# PhotoSensor.net
KiCad netlist of a schematic drawn in Altium Designer
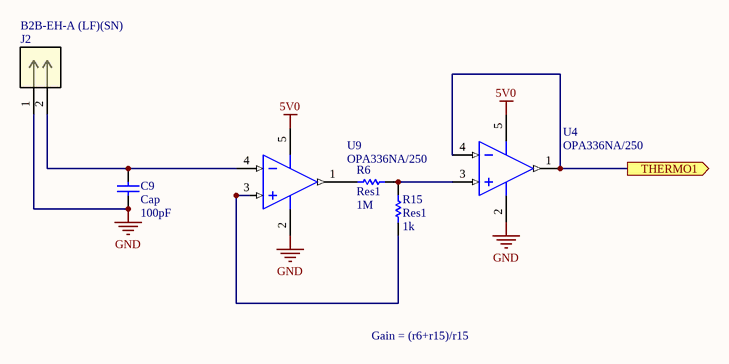
[diagram p0: PhotoSensor.SchDoc]

(export (version "E")
  (design (tool "Eeschema 10.0.6"))
  (components
    (comp (ref "C9")
      (value "Cap")
      (footprint "RAD-0.3")
      (description "Capacitor")
      (fields (field (name "ALTIUM_VALUE") "100pF") (field (name "PUBLISHER") "Altium Limited"))
      (libsource (lib "Miscellaneous Devices") (part "Cap"))
    )
    (comp (ref "J2")
      (value "B2B-EH-A (LF)(SN)")
      (footprint "CONN_B2B-EH-A (LF)(SN)_JST")
      (description "No Description Available")
      (fields (field (name "COPYRIGHT") "Copyright (C) 2018 Accelerated Designs. All rights reserved"))
      (libsource (lib "2020-09-22_22-27-35") (part "B2B-EH-A (LF)(SN)"))
    )
    (comp (ref "R6")
      (value "Res1")
      (footprint "AXIAL-0.3")
      (description "Resistor")
      (fields (field (name "ALTIUM_VALUE") "1M") (field (name "PUBLISHER") "Altium Limited"))
      (libsource (lib "Miscellaneous Devices") (part "Res1"))
    )
    (comp (ref "R15")
      (value "Res1")
      (footprint "AXIAL-0.3")
      (description "Resistor")
      (fields (field (name "ALTIUM_VALUE") "1k") (field (name "PUBLISHER") "Altium Limited"))
      (libsource (lib "Miscellaneous Devices") (part "Res1"))
    )
    (comp (ref "U4")
      (value "OPA336NA/250")
      (footprint "DBV0005A_M")
      (fields (field (name "MANUFACTURER") "Texas Instruments"))
      (libsource (lib "Altium Content Vault") (part "TI-OPA_SM7XXXX-DBV5"))
    )
    (comp (ref "U9")
      (value "OPA336NA/250")
      (footprint "DBV0005A_M")
      (fields (field (name "MANUFACTURER") "Texas Instruments"))
      (libsource (lib "Altium Content Vault") (part "TI-OPA_SM7XXXX-DBV5"))
    )
  )
  (nets
    (net (code "1") (name "/THERMO1") (class "Default")
      (node (ref "U4") (pin "1") (pinfunction "OUT_1") (pintype "output"))
      (node (ref "U4") (pin "4") (pinfunction "IN-_4") (pintype "input"))
    )
    (net (code "2") (name "5V0") (class "Default")
      (node (ref "U4") (pin "5") (pinfunction "V+_5") (pintype "power_in"))
      (node (ref "U9") (pin "5") (pinfunction "V+_5") (pintype "power_in"))
    )
    (net (code "3") (name "GND") (class "Default")
      (node (ref "C9") (pin "1") (pinfunction "1_1") (pintype "passive"))
      (node (ref "J2") (pin "1") (pinfunction "1_1") (pintype "passive"))
      (node (ref "U4") (pin "2") (pinfunction "V-_2") (pintype "power_in"))
      (node (ref "U9") (pin "2") (pinfunction "V-_2") (pintype "power_in"))
    )
    (net (code "4") (name "Net-(U4-IN+)") (class "Default")
      (node (ref "R15") (pin "1") (pinfunction "1_1") (pintype "passive"))
      (node (ref "R6") (pin "1") (pinfunction "1_1") (pintype "passive"))
      (node (ref "U4") (pin "3") (pinfunction "IN+_3") (pintype "input"))
    )
    (net (code "5") (name "Net-(U9-IN+)") (class "Default")
      (node (ref "R15") (pin "2") (pinfunction "2_2") (pintype "passive"))
      (node (ref "U9") (pin "3") (pinfunction "IN+_3") (pintype "input"))
    )
    (net (code "6") (name "Net-(U9-IN-)") (class "Default")
      (node (ref "C9") (pin "2") (pinfunction "2_2") (pintype "passive"))
      (node (ref "J2") (pin "2") (pinfunction "2_2") (pintype "passive"))
      (node (ref "U9") (pin "4") (pinfunction "IN-_4") (pintype "input"))
    )
    (net (code "7") (name "Net-(U9-OUT)") (class "Default")
      (node (ref "R6") (pin "2") (pinfunction "2_2") (pintype "passive"))
      (node (ref "U9") (pin "1") (pinfunction "OUT_1") (pintype "output"))
    )
  )
)
